# pa97.net
KiCad netlist of a schematic drawn in EAGLE
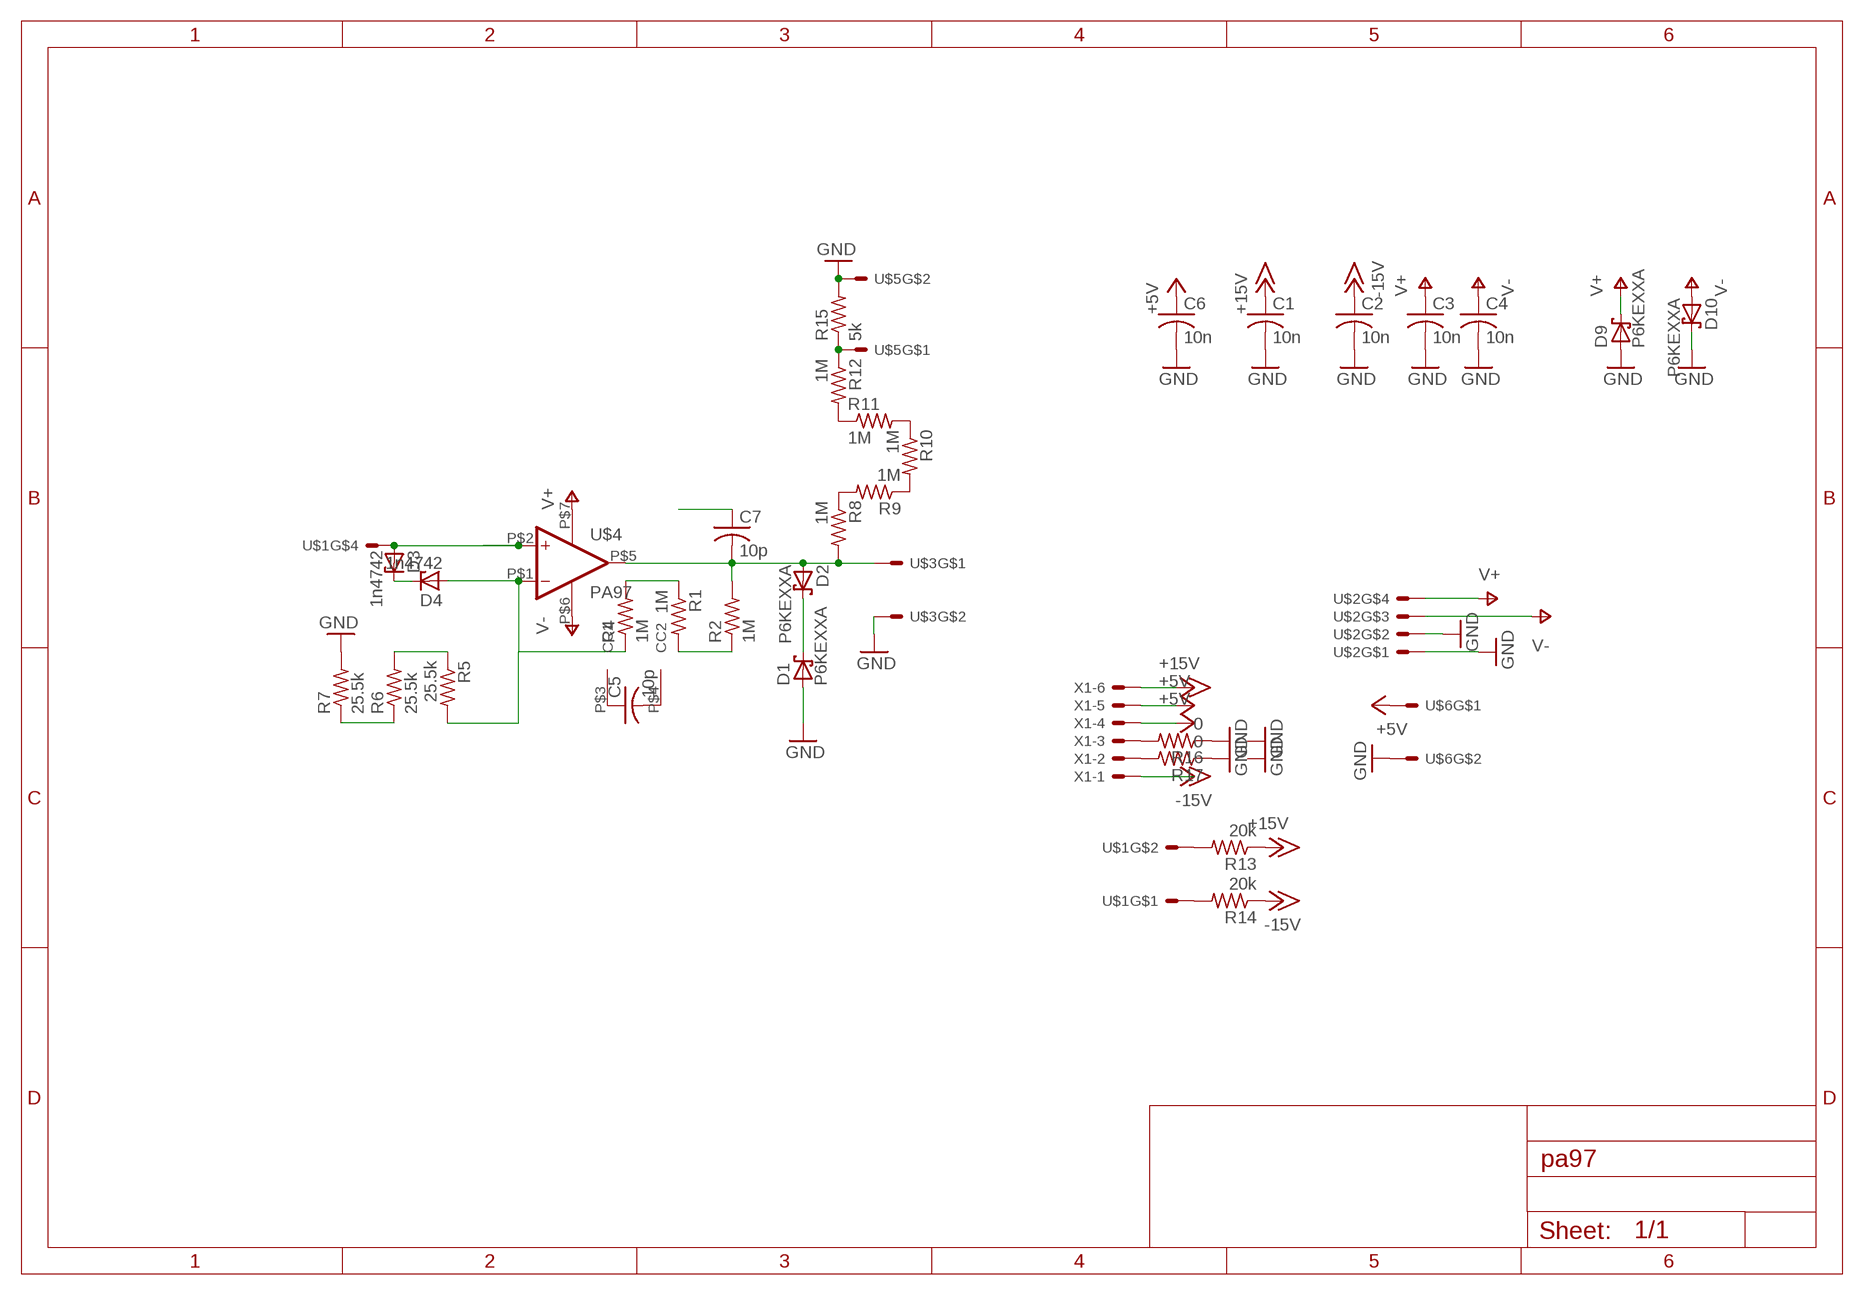
[diagram p0: schematic, sheet 1]

(export (version "E")
  (design (tool "Eeschema 10.0.6"))
  (components
    (comp (ref "C1")
      (value "10n")
      (footprint "eagle-import:C075-032X103")
      (libsource (lib "eagle-import") (part "C-US075-032X103"))
    )
    (comp (ref "C2")
      (value "10n")
      (footprint "eagle-import:C075-032X103")
      (libsource (lib "eagle-import") (part "C-US075-032X103"))
    )
    (comp (ref "C3")
      (value "10n")
      (footprint "eagle-import:C075-032X103")
      (libsource (lib "eagle-import") (part "C-US075-032X103"))
    )
    (comp (ref "C4")
      (value "10n")
      (footprint "eagle-import:C075-032X103")
      (libsource (lib "eagle-import") (part "C-US075-032X103"))
    )
    (comp (ref "C5")
      (value "10p")
      (footprint "eagle-import:C075-032X103")
      (libsource (lib "eagle-import") (part "C-US075-032X103"))
    )
    (comp (ref "C6")
      (value "10n")
      (footprint "eagle-import:C075-032X103")
      (libsource (lib "eagle-import") (part "C-US075-032X103"))
    )
    (comp (ref "C7")
      (value "10p")
      (footprint "eagle-import:C075-032X103")
      (libsource (lib "eagle-import") (part "C-US075-032X103"))
    )
    (comp (ref "D1")
      (value "P6KEXXA")
      (footprint "eagle-import:C1702-15")
      (libsource (lib "eagle-import") (part "P6KEXXA"))
    )
    (comp (ref "D2")
      (value "P6KEXXA")
      (footprint "eagle-import:C1702-15")
      (libsource (lib "eagle-import") (part "P6KEXXA"))
    )
    (comp (ref "D3")
      (value "1n4742")
      (footprint "eagle-import:DO41Z10")
      (libsource (lib "eagle-import") (part "ZENER-DIODEDO41Z10"))
    )
    (comp (ref "D4")
      (value "1n4742")
      (footprint "eagle-import:DO41Z10")
      (libsource (lib "eagle-import") (part "ZENER-DIODEDO41Z10"))
    )
    (comp (ref "D9")
      (value "P6KEXXA")
      (footprint "eagle-import:C1702-15")
      (libsource (lib "eagle-import") (part "P6KEXXA"))
    )
    (comp (ref "D10")
      (value "P6KEXXA")
      (footprint "eagle-import:C1702-15")
      (libsource (lib "eagle-import") (part "P6KEXXA"))
    )
    (comp (ref "R1")
      (value "1M")
      (footprint "eagle-import:0207_10")
      (libsource (lib "eagle-import") (part "R-US_0207/10"))
    )
    (comp (ref "R2")
      (value "1M")
      (footprint "eagle-import:0207_10")
      (libsource (lib "eagle-import") (part "R-US_0207/10"))
    )
    (comp (ref "R4")
      (value "1M")
      (footprint "eagle-import:0207_10")
      (libsource (lib "eagle-import") (part "R-US_0207/10"))
    )
    (comp (ref "R5")
      (value "25.5k")
      (footprint "eagle-import:0207_10")
      (libsource (lib "eagle-import") (part "R-US_0207/10"))
    )
    (comp (ref "R6")
      (value "25.5k")
      (footprint "eagle-import:0207_10")
      (libsource (lib "eagle-import") (part "R-US_0207/10"))
    )
    (comp (ref "R7")
      (value "25.5k")
      (footprint "eagle-import:0207_10")
      (libsource (lib "eagle-import") (part "R-US_0207/10"))
    )
    (comp (ref "R8")
      (value "1M")
      (footprint "eagle-import:0207_10")
      (libsource (lib "eagle-import") (part "R-US_0207/10"))
    )
    (comp (ref "R9")
      (value "1M")
      (footprint "eagle-import:0207_10")
      (libsource (lib "eagle-import") (part "R-US_0207/10"))
    )
    (comp (ref "R10")
      (value "1M")
      (footprint "eagle-import:0207_10")
      (libsource (lib "eagle-import") (part "R-US_0207/10"))
    )
    (comp (ref "R11")
      (value "1M")
      (footprint "eagle-import:0207_10")
      (libsource (lib "eagle-import") (part "R-US_0207/10"))
    )
    (comp (ref "R12")
      (value "1M")
      (footprint "eagle-import:0207_10")
      (libsource (lib "eagle-import") (part "R-US_0207/10"))
    )
    (comp (ref "R13")
      (value "20k")
      (footprint "eagle-import:0207_10")
      (libsource (lib "eagle-import") (part "R-US_0207/10"))
    )
    (comp (ref "R14")
      (value "20k")
      (footprint "eagle-import:0207_10")
      (libsource (lib "eagle-import") (part "R-US_0207/10"))
    )
    (comp (ref "R15")
      (value "5k")
      (footprint "eagle-import:0207_10")
      (libsource (lib "eagle-import") (part "R-US_0207/10"))
    )
    (comp (ref "R16")
      (value "0")
      (footprint "eagle-import:0207_10")
      (libsource (lib "eagle-import") (part "R-US_0207/10"))
    )
    (comp (ref "R17")
      (value "0")
      (footprint "eagle-import:0207_10")
      (libsource (lib "eagle-import") (part "R-US_0207/10"))
    )
    (comp (ref "U$1")
      (value "5569-4")
      (footprint "eagle-import:5669-4")
      (libsource (lib "eagle-import") (part "5569-4"))
    )
    (comp (ref "U$2")
      (value "5569-4")
      (footprint "eagle-import:5669-4")
      (libsource (lib "eagle-import") (part "5569-4"))
    )
    (comp (ref "U$3")
      (value "5569-2")
      (footprint "eagle-import:5569-2")
      (libsource (lib "eagle-import") (part "5569-2"))
    )
    (comp (ref "U$4")
      (value "PA97")
      (footprint "eagle-import:7SIP")
      (libsource (lib "eagle-import") (part "PA97"))
    )
    (comp (ref "U$5")
      (value "5569-2")
      (footprint "eagle-import:5569-2")
      (libsource (lib "eagle-import") (part "5569-2"))
    )
    (comp (ref "U$6")
      (value "5569-2")
      (footprint "eagle-import:5569-2")
      (libsource (lib "eagle-import") (part "5569-2"))
    )
    (comp (ref "X1")
      (value "KK-156-6")
      (footprint "eagle-import:KK-156-6")
      (libsource (lib "eagle-import") (part "KK-156-6"))
    )
  )
  (nets
    (net (code "1") (name "+5V") (class "Default")
      (node (ref "C6") (pin "1") (pinfunction "1_1") (pintype "passive"))
      (node (ref "U$6") (pin "P$1") (pinfunction "S_P$1") (pintype "passive"))
      (node (ref "X1") (pin "4") (pinfunction "S_4") (pintype "passive"))
      (node (ref "X1") (pin "5") (pinfunction "S_5") (pintype "passive"))
    )
    (net (code "2") (name "+15V") (class "Default")
      (node (ref "C1") (pin "1") (pinfunction "1_1") (pintype "passive"))
      (node (ref "R13") (pin "1") (pinfunction "1_1") (pintype "passive"))
      (node (ref "X1") (pin "6") (pinfunction "S_6") (pintype "passive"))
    )
    (net (code "3") (name "-15V") (class "Default")
      (node (ref "C2") (pin "1") (pinfunction "1_1") (pintype "passive"))
      (node (ref "R14") (pin "1") (pinfunction "1_1") (pintype "passive"))
      (node (ref "X1") (pin "1") (pinfunction "S_1") (pintype "passive"))
    )
    (net (code "4") (name "GND") (class "Default")
      (node (ref "C1") (pin "2") (pinfunction "2_2") (pintype "passive"))
      (node (ref "C2") (pin "2") (pinfunction "2_2") (pintype "passive"))
      (node (ref "C3") (pin "2") (pinfunction "2_2") (pintype "passive"))
      (node (ref "C4") (pin "2") (pinfunction "2_2") (pintype "passive"))
      (node (ref "C6") (pin "2") (pinfunction "2_2") (pintype "passive"))
      (node (ref "D1") (pin "A") (pinfunction "A_A") (pintype "passive"))
      (node (ref "D10") (pin "C") (pinfunction "C_C") (pintype "passive"))
      (node (ref "D9") (pin "A") (pinfunction "A_A") (pintype "passive"))
      (node (ref "R15") (pin "2") (pinfunction "2_2") (pintype "passive"))
      (node (ref "R16") (pin "1") (pinfunction "1_1") (pintype "passive"))
      (node (ref "R17") (pin "1") (pinfunction "1_1") (pintype "passive"))
      (node (ref "R7") (pin "2") (pinfunction "2_2") (pintype "passive"))
      (node (ref "U$2") (pin "P$1") (pinfunction "S_P$1") (pintype "passive"))
      (node (ref "U$2") (pin "P$2") (pinfunction "S_P$2") (pintype "passive"))
      (node (ref "U$3") (pin "P$2") (pinfunction "S_P$2") (pintype "passive"))
      (node (ref "U$5") (pin "P$2") (pinfunction "S_P$2") (pintype "passive"))
      (node (ref "U$6") (pin "P$2") (pinfunction "S_P$2") (pintype "passive"))
    )
    (net (code "5") (name "Net-(D1-PadC)") (class "Default")
      (node (ref "D1") (pin "C") (pinfunction "C_C") (pintype "passive"))
      (node (ref "D2") (pin "C") (pinfunction "C_C") (pintype "passive"))
    )
    (net (code "6") (name "Net-(D3-PadC)") (class "Default")
      (node (ref "D3") (pin "C") (pinfunction "C_C") (pintype "passive"))
      (node (ref "D4") (pin "C") (pinfunction "C_C") (pintype "passive"))
    )
    (net (code "7") (name "Net-(R1-Pad1)") (class "Default")
      (node (ref "R1") (pin "1") (pinfunction "1_1") (pintype "passive"))
      (node (ref "R4") (pin "2") (pinfunction "2_2") (pintype "passive"))
    )
    (net (code "8") (name "Net-(R1-Pad2)") (class "Default")
      (node (ref "R1") (pin "2") (pinfunction "2_2") (pintype "passive"))
      (node (ref "R2") (pin "1") (pinfunction "1_1") (pintype "passive"))
    )
    (net (code "9") (name "Net-(R5-Pad1)") (class "Default")
      (node (ref "R5") (pin "1") (pinfunction "1_1") (pintype "passive"))
      (node (ref "R6") (pin "2") (pinfunction "2_2") (pintype "passive"))
    )
    (net (code "10") (name "Net-(R6-Pad1)") (class "Default")
      (node (ref "R6") (pin "1") (pinfunction "1_1") (pintype "passive"))
      (node (ref "R7") (pin "1") (pinfunction "1_1") (pintype "passive"))
    )
    (net (code "11") (name "Net-(R8-Pad1)") (class "Default")
      (node (ref "R8") (pin "1") (pinfunction "1_1") (pintype "passive"))
      (node (ref "R9") (pin "2") (pinfunction "2_2") (pintype "passive"))
    )
    (net (code "12") (name "Net-(R10-Pad1)") (class "Default")
      (node (ref "R10") (pin "1") (pinfunction "1_1") (pintype "passive"))
      (node (ref "R11") (pin "2") (pinfunction "2_2") (pintype "passive"))
    )
    (net (code "13") (name "Net-(R10-Pad2)") (class "Default")
      (node (ref "R10") (pin "2") (pinfunction "2_2") (pintype "passive"))
      (node (ref "R9") (pin "1") (pinfunction "1_1") (pintype "passive"))
    )
    (net (code "14") (name "Net-(R11-Pad1)") (class "Default")
      (node (ref "R11") (pin "1") (pinfunction "1_1") (pintype "passive"))
      (node (ref "R12") (pin "2") (pinfunction "2_2") (pintype "passive"))
    )
    (net (code "15") (name "Net-(U$1A-S)") (class "Default")
      (node (ref "R14") (pin "2") (pinfunction "2_2") (pintype "passive"))
      (node (ref "U$1") (pin "P$1") (pinfunction "S_P$1") (pintype "passive"))
    )
    (net (code "16") (name "Net-(U$1B-S)") (class "Default")
      (node (ref "R13") (pin "2") (pinfunction "2_2") (pintype "passive"))
      (node (ref "U$1") (pin "P$2") (pinfunction "S_P$2") (pintype "passive"))
    )
    (net (code "17") (name "Net-(U$1D-S)") (class "Default")
      (node (ref "D3") (pin "A") (pinfunction "A_A") (pintype "passive"))
      (node (ref "U$1") (pin "P$4") (pinfunction "S_P$4") (pintype "passive"))
      (node (ref "U$4") (pin "P$2") (pinfunction "+IN_P$2") (pintype "input"))
    )
    (net (code "18") (name "Net-(U$3A-S)") (class "Default")
      (node (ref "C7") (pin "2") (pinfunction "2_2") (pintype "passive"))
      (node (ref "D2") (pin "A") (pinfunction "A_A") (pintype "passive"))
      (node (ref "R2") (pin "2") (pinfunction "2_2") (pintype "passive"))
      (node (ref "R8") (pin "2") (pinfunction "2_2") (pintype "passive"))
      (node (ref "U$3") (pin "P$1") (pinfunction "S_P$1") (pintype "passive"))
      (node (ref "U$4") (pin "P$5") (pinfunction "OUT_P$5") (pintype "output"))
    )
    (net (code "19") (name "Net-(U$4--IN)") (class "Default")
      (node (ref "D4") (pin "A") (pinfunction "A_A") (pintype "passive"))
      (node (ref "R4") (pin "1") (pinfunction "1_1") (pintype "passive"))
      (node (ref "R5") (pin "2") (pinfunction "2_2") (pintype "passive"))
      (node (ref "U$4") (pin "P$1") (pinfunction "-IN_P$1") (pintype "input"))
    )
    (net (code "20") (name "Net-(U$4-CC1)") (class "Default")
      (node (ref "C5") (pin "1") (pinfunction "1_1") (pintype "passive"))
      (node (ref "U$4") (pin "P$3") (pinfunction "CC1_P$3") (pintype "bidirectional"))
    )
    (net (code "21") (name "Net-(U$4-CC2)") (class "Default")
      (node (ref "C5") (pin "2") (pinfunction "2_2") (pintype "passive"))
      (node (ref "U$4") (pin "P$4") (pinfunction "CC2_P$4") (pintype "bidirectional"))
    )
    (net (code "22") (name "Net-(U$5A-S)") (class "Default")
      (node (ref "R12") (pin "1") (pinfunction "1_1") (pintype "passive"))
      (node (ref "R15") (pin "1") (pinfunction "1_1") (pintype "passive"))
      (node (ref "U$5") (pin "P$1") (pinfunction "S_P$1") (pintype "passive"))
    )
    (net (code "23") (name "Net-(X1B-S)") (class "Default")
      (node (ref "R17") (pin "2") (pinfunction "2_2") (pintype "passive"))
      (node (ref "X1") (pin "2") (pinfunction "S_2") (pintype "passive"))
    )
    (net (code "24") (name "Net-(X1C-S)") (class "Default")
      (node (ref "R16") (pin "2") (pinfunction "2_2") (pintype "passive"))
      (node (ref "X1") (pin "3") (pinfunction "S_3") (pintype "passive"))
    )
    (net (code "25") (name "V+") (class "Default")
      (node (ref "C3") (pin "1") (pinfunction "1_1") (pintype "passive"))
      (node (ref "D9") (pin "C") (pinfunction "C_C") (pintype "passive"))
      (node (ref "U$2") (pin "P$4") (pinfunction "S_P$4") (pintype "passive"))
      (node (ref "U$4") (pin "P$7") (pinfunction "V+_P$7") (pintype "power_in"))
    )
    (net (code "26") (name "V-") (class "Default")
      (node (ref "C4") (pin "1") (pinfunction "1_1") (pintype "passive"))
      (node (ref "D10") (pin "A") (pinfunction "A_A") (pintype "passive"))
      (node (ref "U$2") (pin "P$3") (pinfunction "S_P$3") (pintype "passive"))
      (node (ref "U$4") (pin "P$6") (pinfunction "V-_P$6") (pintype "power_in"))
    )
    (net (code "27") (name "unconnected-(C7-Pad1)") (class "Default")
      (node (ref "C7") (pin "1") (pinfunction "1_1") (pintype "passive"))
    )
  )
)
